# MOTOR_CONTROL.net
KiCad netlist of a schematic drawn in Altium Designer
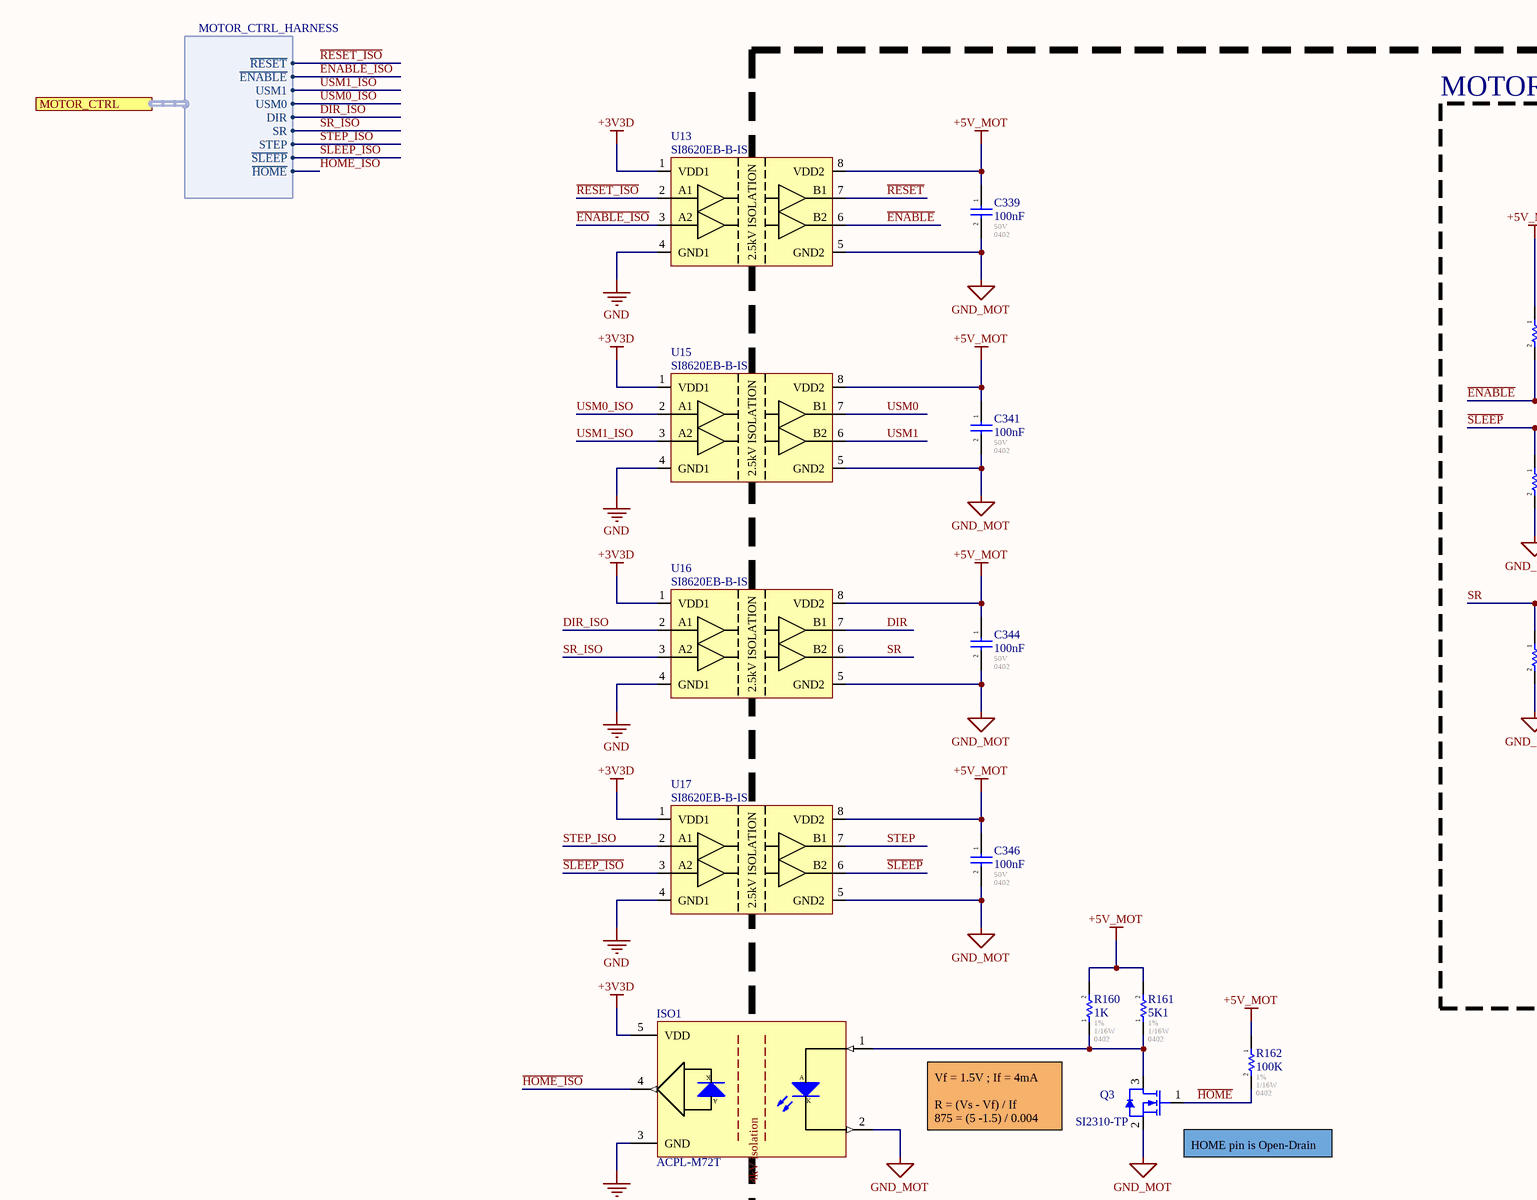
[diagram p0: MOTOR_CONTROL.SchDoc, top left]
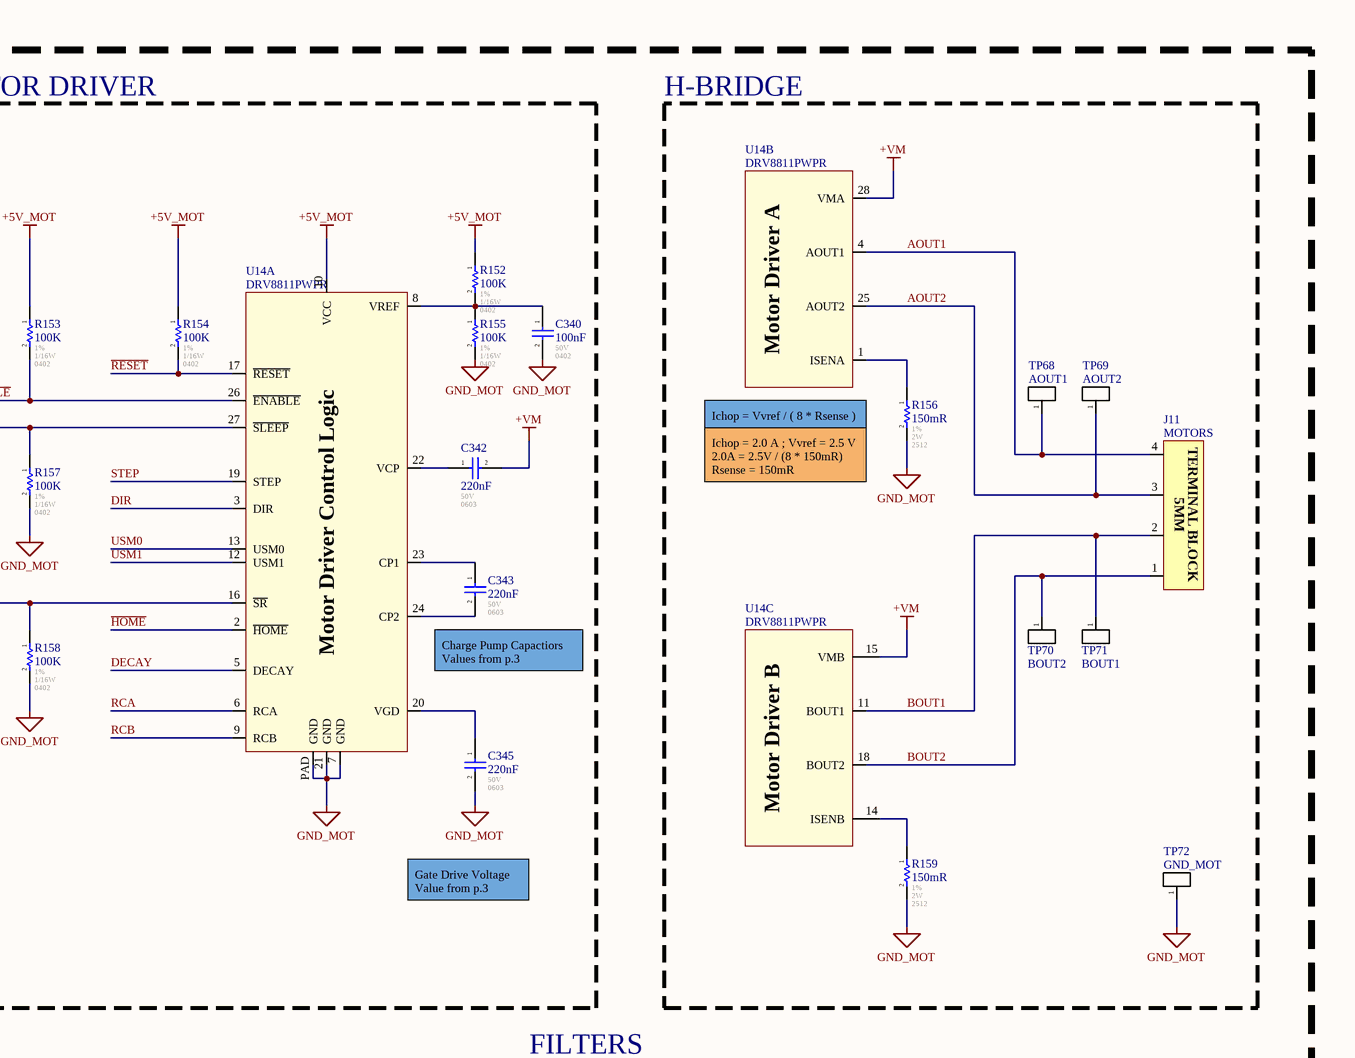
[diagram p1: MOTOR_CONTROL.SchDoc, top right]
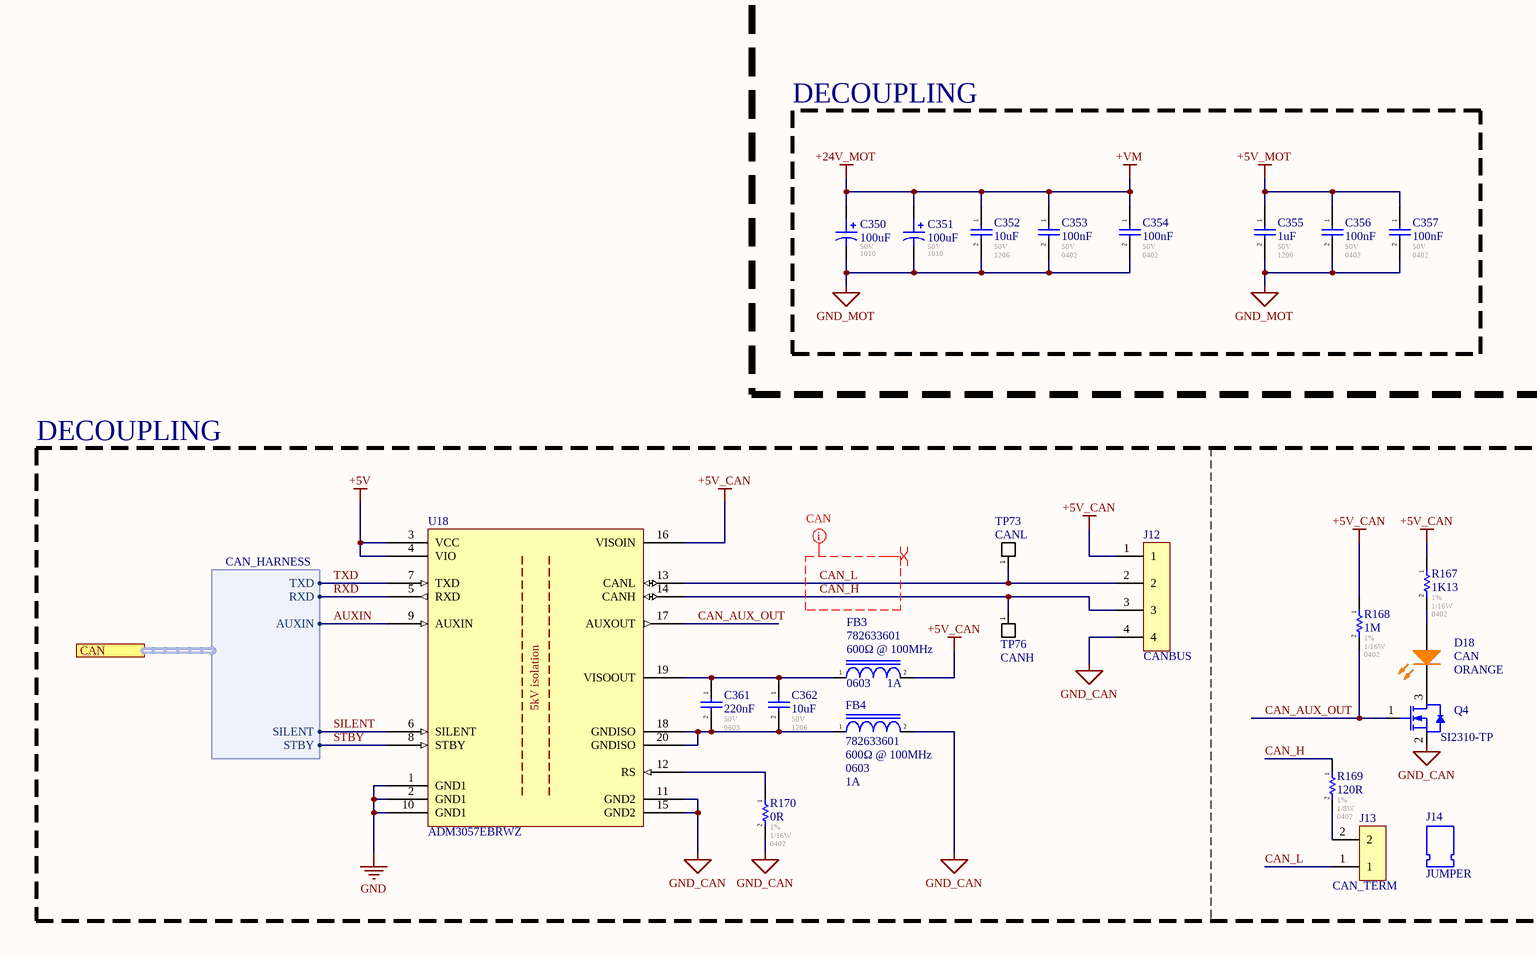
[diagram p2: MOTOR_CONTROL.SchDoc, bottom left]
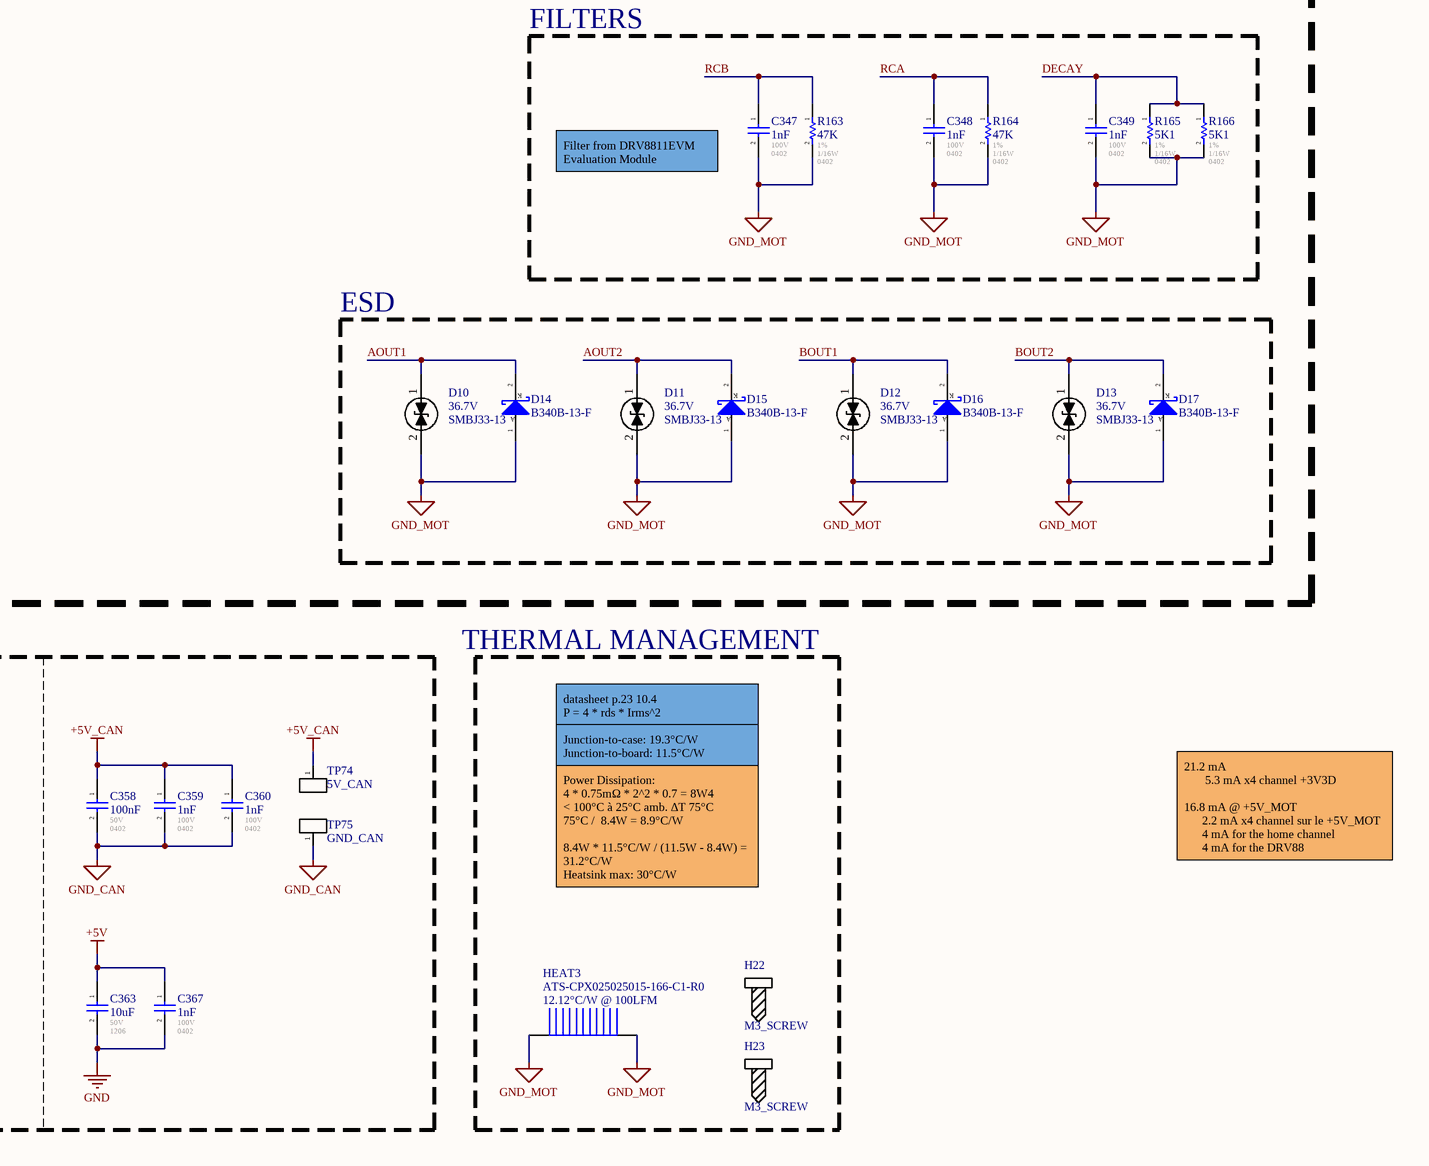
[diagram p3: MOTOR_CONTROL.SchDoc, bottom right]

(export (version "E")
  (design (tool "Eeschema 10.0.6"))
  (components
    (comp (ref "C339")
      (value "100nF")
      (footprint "0402")
      (description "GCM155R71H104KE02J\r\n0402 100nF 10% X7R Ceramic Capacitor")
      (fields
        (field (name "MFR") "Murata")
        (field (name "PART#") "GCM155R71H104KE02J")
        (field (name "VOLTAGE - RATED") "50V")
      )
      (libsource (lib "Symbols") (part "CAP_CER"))
    )
    (comp (ref "C340")
      (value "100nF")
      (footprint "0402")
      (description "GCM155R71H104KE02J\r\n0402 100nF 10% X7R Ceramic Capacitor")
      (fields
        (field (name "MFR") "Murata")
        (field (name "PART#") "GCM155R71H104KE02J")
        (field (name "VOLTAGE - RATED") "50V")
      )
      (libsource (lib "Symbols") (part "CAP_CER"))
    )
    (comp (ref "C341")
      (value "100nF")
      (footprint "0402")
      (description "GCM155R71H104KE02J\r\n0402 100nF 10% X7R Ceramic Capacitor")
      (fields
        (field (name "MFR") "Murata")
        (field (name "PART#") "GCM155R71H104KE02J")
        (field (name "VOLTAGE - RATED") "50V")
      )
      (libsource (lib "Symbols") (part "CAP_CER"))
    )
    (comp (ref "C342")
      (value "220nF")
      (footprint "0603")
      (description "GCM188R71H224KA64D\r\n0603 220nF 10% X7R Ceramic Capacitor")
      (fields
        (field (name "MFR") "Murata")
        (field (name "PART#") "GCM188R71H224KA64D")
        (field (name "VOLTAGE - RATED") "50V")
      )
      (libsource (lib "Symbols") (part "CAP_CER"))
    )
    (comp (ref "C343")
      (value "220nF")
      (footprint "0603")
      (description "GCM188R71H224KA64D\r\n0603 220nF 10% X7R Ceramic Capacitor")
      (fields
        (field (name "MFR") "Murata")
        (field (name "PART#") "GCM188R71H224KA64D")
        (field (name "VOLTAGE - RATED") "50V")
      )
      (libsource (lib "Symbols") (part "CAP_CER"))
    )
    (comp (ref "C344")
      (value "100nF")
      (footprint "0402")
      (description "GCM155R71H104KE02J\r\n0402 100nF 10% X7R Ceramic Capacitor")
      (fields
        (field (name "MFR") "Murata")
        (field (name "PART#") "GCM155R71H104KE02J")
        (field (name "VOLTAGE - RATED") "50V")
      )
      (libsource (lib "Symbols") (part "CAP_CER"))
    )
    (comp (ref "C345")
      (value "220nF")
      (footprint "0603")
      (description "GCM188R71H224KA64D\r\n0603 220nF 10% X7R Ceramic Capacitor")
      (fields
        (field (name "MFR") "Murata")
        (field (name "PART#") "GCM188R71H224KA64D")
        (field (name "VOLTAGE - RATED") "50V")
      )
      (libsource (lib "Symbols") (part "CAP_CER"))
    )
    (comp (ref "C346")
      (value "100nF")
      (footprint "0402")
      (description "GCM155R71H104KE02J\r\n0402 100nF 10% X7R Ceramic Capacitor")
      (fields
        (field (name "MFR") "Murata")
        (field (name "PART#") "GCM155R71H104KE02J")
        (field (name "VOLTAGE - RATED") "50V")
      )
      (libsource (lib "Symbols") (part "CAP_CER"))
    )
    (comp (ref "C347")
      (value "1nF")
      (footprint "0402")
      (description "GCM155R72A102KA37D\r\n0402 1nF 10% X7R Ceramic Capacitor")
      (fields
        (field (name "MFR") "Murata")
        (field (name "PART#") "GCM155R72A102KA37D")
        (field (name "VOLTAGE - RATED") "100V")
      )
      (libsource (lib "Symbols") (part "CAP_CER"))
    )
    (comp (ref "C348")
      (value "1nF")
      (footprint "0402")
      (description "GCM155R72A102KA37D\r\n0402 1nF 10% X7R Ceramic Capacitor")
      (fields
        (field (name "MFR") "Murata")
        (field (name "PART#") "GCM155R72A102KA37D")
        (field (name "VOLTAGE - RATED") "100V")
      )
      (libsource (lib "Symbols") (part "CAP_CER"))
    )
    (comp (ref "C349")
      (value "1nF")
      (footprint "0402")
      (description "GCM155R72A102KA37D\r\n0402 1nF 10% X7R Ceramic Capacitor")
      (fields
        (field (name "MFR") "Murata")
        (field (name "PART#") "GCM155R72A102KA37D")
        (field (name "VOLTAGE - RATED") "100V")
      )
      (libsource (lib "Symbols") (part "CAP_CER"))
    )
    (comp (ref "C350")
      (value "100uF")
      (footprint "CAP_ALU_1010_vishay")
      (description "CAP - ALU 100uF 20% 50V - 1010")
      (fields
        (field (name "MFG") "Vishay Dale")
        (field (name "MFG PART NUMBER") "MAL215099101E3")
        (field (name "VOLTAGE") "50V")
        (field (name "PACKAGE") "1010")
        (field (name "CREATEDBY") "Jonathan Bouchard")
      )
      (libsource (lib "S7CAS_LIB2023") (part "CAP_ALU_MAL215099101E3"))
    )
    (comp (ref "C351")
      (value "100uF")
      (footprint "CAP_ALU_1010_vishay")
      (description "CAP - ALU 100uF 20% 50V - 1010")
      (fields
        (field (name "MFG") "Vishay Dale")
        (field (name "MFG PART NUMBER") "MAL215099101E3")
        (field (name "VOLTAGE") "50V")
        (field (name "PACKAGE") "1010")
        (field (name "CREATEDBY") "Jonathan Bouchard")
      )
      (libsource (lib "S7CAS_LIB2023") (part "CAP_ALU_MAL215099101E3"))
    )
    (comp (ref "C352")
      (value "10uF")
      (footprint "1206")
      (description "GRT31CR61H106KE01L\r\n1206 10uF 10% X5R Ceramic Capacitor")
      (fields
        (field (name "MFR") "Murata")
        (field (name "VOLTAGE - RATED") "50V")
        (field (name "TOLERANCE") "10%")
      )
      (libsource (lib "Symbols") (part "CAP_CER"))
    )
    (comp (ref "C353")
      (value "100nF")
      (footprint "0402")
      (description "GCM155R71H104KE02J\r\n0402 100nF 10% X7R Ceramic Capacitor")
      (fields
        (field (name "MFR") "Murata")
        (field (name "PART#") "GCM155R71H104KE02J")
        (field (name "VOLTAGE - RATED") "50V")
      )
      (libsource (lib "Symbols") (part "CAP_CER"))
    )
    (comp (ref "C354")
      (value "100nF")
      (footprint "0402")
      (description "GCM155R71H104KE02J\r\n0402 100nF 10% X7R Ceramic Capacitor")
      (fields
        (field (name "MFR") "Murata")
        (field (name "PART#") "GCM155R71H104KE02J")
        (field (name "VOLTAGE - RATED") "50V")
      )
      (libsource (lib "Symbols") (part "CAP_CER"))
    )
    (comp (ref "C355")
      (value "1uF")
      (footprint "1206")
      (description "GCJ31CR71H105KA12L\r\n1206 1uF 10% X7R Ceramic Capacitor")
      (fields
        (field (name "MFR") "Murata")
        (field (name "PART#") "GCJ31CR71H105KA12L")
        (field (name "VOLTAGE - RATED") "50V")
      )
      (libsource (lib "Symbols") (part "CAP_CER"))
    )
    (comp (ref "C356")
      (value "100nF")
      (footprint "0402")
      (description "GCM155R71H104KE02J\r\n0402 100nF 10% X7R Ceramic Capacitor")
      (fields
        (field (name "MFR") "Murata")
        (field (name "PART#") "GCM155R71H104KE02J")
        (field (name "VOLTAGE - RATED") "50V")
      )
      (libsource (lib "Symbols") (part "CAP_CER"))
    )
    (comp (ref "C357")
      (value "100nF")
      (footprint "0402")
      (description "GCM155R71H104KE02J\r\n0402 100nF 10% X7R Ceramic Capacitor")
      (fields
        (field (name "MFR") "Murata")
        (field (name "PART#") "GCM155R71H104KE02J")
        (field (name "VOLTAGE - RATED") "50V")
      )
      (libsource (lib "Symbols") (part "CAP_CER"))
    )
    (comp (ref "C358")
      (value "100nF")
      (footprint "0402")
      (description "GCM155R71H104KE02J\r\n0402 100nF 10% X7R Ceramic Capacitor")
      (fields
        (field (name "MFR") "Murata")
        (field (name "PART#") "GCM155R71H104KE02J")
        (field (name "VOLTAGE - RATED") "50V")
      )
      (libsource (lib "Symbols") (part "CAP_CER"))
    )
    (comp (ref "C359")
      (value "1nF")
      (footprint "0402")
      (description "GCM155R72A102KA37D\r\n0402 1nF 10% X7R Ceramic Capacitor")
      (fields
        (field (name "MFR") "Murata")
        (field (name "PART#") "GCM155R72A102KA37D")
        (field (name "VOLTAGE - RATED") "100V")
      )
      (libsource (lib "Symbols") (part "CAP_CER"))
    )
    (comp (ref "C360")
      (value "1nF")
      (footprint "0402")
      (description "GCM155R72A102KA37D\r\n0402 1nF 10% X7R Ceramic Capacitor")
      (fields
        (field (name "MFR") "Murata")
        (field (name "PART#") "GCM155R72A102KA37D")
        (field (name "VOLTAGE - RATED") "100V")
      )
      (libsource (lib "Symbols") (part "CAP_CER"))
    )
    (comp (ref "C361")
      (value "220nF")
      (footprint "0603")
      (description "GCM188R71H224KA64D\r\n0603 220nF 10% X7R Ceramic Capacitor")
      (fields
        (field (name "MFR") "Murata")
        (field (name "PART#") "GCM188R71H224KA64D")
        (field (name "VOLTAGE - RATED") "50V")
      )
      (libsource (lib "Symbols") (part "CAP_CER"))
    )
    (comp (ref "C362")
      (value "10uF")
      (footprint "1206")
      (description "GRT31CR61H106KE01L\r\n1206 10uF 10% X5R Ceramic Capacitor")
      (fields
        (field (name "MFR") "Murata")
        (field (name "VOLTAGE - RATED") "50V")
        (field (name "TOLERANCE") "10%")
      )
      (libsource (lib "Symbols") (part "CAP_CER"))
    )
    (comp (ref "C363")
      (value "10uF")
      (footprint "1206")
      (description "GRT31CR61H106KE01L\r\n1206 10uF 10% X5R Ceramic Capacitor")
      (fields
        (field (name "MFR") "Murata")
        (field (name "VOLTAGE - RATED") "50V")
        (field (name "TOLERANCE") "10%")
      )
      (libsource (lib "Symbols") (part "CAP_CER"))
    )
    (comp (ref "C367")
      (value "1nF")
      (footprint "0402")
      (description "GCM155R72A102KA37D\r\n0402 1nF 10% X7R Ceramic Capacitor")
      (fields
        (field (name "MFR") "Murata")
        (field (name "PART#") "GCM155R72A102KA37D")
        (field (name "VOLTAGE - RATED") "100V")
      )
      (libsource (lib "Symbols") (part "CAP_CER"))
    )
    (comp (ref "D10")
      (value "SMBJ33-13")
      (footprint "DO214AA (SMB)")
      (description "53.3V Clamp 11.3A Ipp Tvs Diode Surface Mount SMB")
      (fields (field (name "MFR") "SMBJ33CAQ-13-F") (field (name "VOLTAGE - BREAKDOWN") "36.7V"))
      (libsource (lib "Symbols") (part "DIODE_TVS"))
    )
    (comp (ref "D11")
      (value "SMBJ33-13")
      (footprint "DO214AA (SMB)")
      (description "53.3V Clamp 11.3A Ipp Tvs Diode Surface Mount SMB")
      (fields (field (name "MFR") "SMBJ33CAQ-13-F") (field (name "VOLTAGE - BREAKDOWN") "36.7V"))
      (libsource (lib "Symbols") (part "DIODE_TVS"))
    )
    (comp (ref "D12")
      (value "SMBJ33-13")
      (footprint "DO214AA (SMB)")
      (description "53.3V Clamp 11.3A Ipp Tvs Diode Surface Mount SMB")
      (fields (field (name "MFR") "SMBJ33CAQ-13-F") (field (name "VOLTAGE - BREAKDOWN") "36.7V"))
      (libsource (lib "Symbols") (part "DIODE_TVS"))
    )
    (comp (ref "D13")
      (value "SMBJ33-13")
      (footprint "DO214AA (SMB)")
      (description "53.3V Clamp 11.3A Ipp Tvs Diode Surface Mount SMB")
      (fields (field (name "MFR") "SMBJ33CAQ-13-F") (field (name "VOLTAGE - BREAKDOWN") "36.7V"))
      (libsource (lib "Symbols") (part "DIODE_TVS"))
    )
    (comp (ref "D14")
      (value "B340B-13-F")
      (footprint "DO214AA (SMB)")
      (description "Generic Shottkey Diode")
      (fields (field (name "MFR") "Diodes Incorporated"))
      (libsource (lib "Symbols") (part "DIODE_SHOTTKEY"))
    )
    (comp (ref "D15")
      (value "B340B-13-F")
      (footprint "DO214AA (SMB)")
      (description "Generic Shottkey Diode")
      (fields (field (name "MFR") "Diodes Incorporated"))
      (libsource (lib "Symbols") (part "DIODE_SHOTTKEY"))
    )
    (comp (ref "D16")
      (value "B340B-13-F")
      (footprint "DO214AA (SMB)")
      (description "Generic Shottkey Diode")
      (fields (field (name "MFR") "Diodes Incorporated"))
      (libsource (lib "Symbols") (part "DIODE_SHOTTKEY"))
    )
    (comp (ref "D17")
      (value "B340B-13-F")
      (footprint "DO214AA (SMB)")
      (description "Generic Shottkey Diode")
      (fields (field (name "MFR") "Diodes Incorporated"))
      (libsource (lib "Symbols") (part "DIODE_SHOTTKEY"))
    )
    (comp (ref "D18")
      (value "CAN")
      (footprint "LED_0603")
      (description "LED - 611nM ORANGE 2mA - 0603")
      (fields
        (field (name "VOLTAGE") "1.8V")
        (field (name "MFG") "ROHM Semiconductor")
        (field (name "ALTIUM_VALUE") "ORANGE")
        (field (name "CREATEDBY") "Jonathan Bouchard")
      )
      (libsource (lib "S7CAS_LIB2023") (part "LED_SML-311DTT86"))
    )
    (comp (ref "FB3")
      (value "782633601")
      (footprint "IND_0603")
      (description "600 Ohms @ 100 MHz 1 Signal Line Ferrite Bead 0603 (1608 Metric) 1A 200mOhm")
      (fields
        (field (name "IMPEDANCE @ FREQ") "600Ω @ 100MHz")
        (field (name "PACKAGE / CASE") "0603")
        (field (name "CURRENT RATING") "1A")
        (field (name "MANUFACTURER") "Wurth Elektronik")
      )
      (libsource (lib "Symbols") (part "FERRITE_BEAD"))
    )
    (comp (ref "FB4")
      (value "782633601")
      (footprint "IND_0603")
      (description "600 Ohms @ 100 MHz 1 Signal Line Ferrite Bead 0603 (1608 Metric) 1A 200mOhm")
      (fields
        (field (name "IMPEDANCE @ FREQ") "600Ω @ 100MHz")
        (field (name "PACKAGE / CASE") "0603")
        (field (name "CURRENT RATING") "1A")
        (field (name "MANUFACTURER") "Wurth Elektronik")
      )
      (libsource (lib "Symbols") (part "FERRITE_BEAD"))
    )
    (comp (ref "H22") (value "M3_SCREW") (libsource (lib "Misc") (part "M3_screw")))
    (comp (ref "H23") (value "M3_SCREW") (libsource (lib "Misc") (part "M3_screw")))
    (comp (ref "HEAT3")
      (value "ATS-CPX025025015-166-C1-R0")
      (footprint "ATS-CPX025025015-166-C1-R0")
      (description "Heatsink Aluminium")
      (fields
        (field (name "MFR") "Advanced Thermal Solutions Inc.")
        (field (name "THERMAL RESISTANCE") "12.12°C/W @ 100LFM")
      )
      (libsource (lib "Misc") (part "HEATSINK_ATS-CPX025025015-166-C1-R0"))
    )
    (comp (ref "ISO1")
      (value "ACPL-M72T")
      (footprint "SOIC-5_4.4MM")
      (description "Logic Output Optoisolator Push-Pull, Totem Pole 4000Vrms 1 Channel 25kV/µs CMTI 5-SO")
      (fields (field (name "MFR") "Broadcom Limited"))
      (libsource (lib "Misc") (part "ACPL-M72T"))
    )
    (comp (ref "J11")
      (value "MOTORS")
      (footprint "CONN_TERMINAL_OSTTA040161")
      (description "CONN -  TERMINAL BLOCK 4POS 5MM - TH")
      (fields
        (field (name "MFG") "On Shore Technology Inc.")
        (field (name "MFG PART NUMBER") "OSTTC040162")
        (field (name "CREATEDBY") "Jonathan Bouchard")
      )
      (libsource (lib "S7CAS_LIB2023") (part "CONN_TERMINAL_OSTTC040162"))
    )
    (comp (ref "J12")
      (value "CANBUS")
      (footprint "HEADER-4_100MIL")
      (libsource (lib "Connectors") (part "HEADER_4"))
    )
    (comp (ref "J13")
      (value "CAN_TERM")
      (footprint "HEADER-2_100MIL")
      (libsource (lib "Connectors") (part "HEADER_2"))
    )
    (comp (ref "J14") (value "JUMPER") (libsource (lib "Misc") (part "JUMPER")))
    (comp (ref "Q3")
      (value "SI2310-TP")
      (footprint "TRX_NMOS_SI2310-TP")
      (description "TRX - MOSFET N-CH 60V 3A - SOT-23")
      (fields
        (field (name "CREATEDBY/DATE") "Louis-Daniel Gaulin / 20-02-2020")
        (field (name "VERIFIEDBY") "C.Paulin - 21/02/2020")
      )
      (libsource (lib "S7CAS_LIB2023") (part "TRX_NMOS_SI2310-TP"))
    )
    (comp (ref "Q4")
      (value "SI2310-TP")
      (footprint "TRX_NMOS_SI2310-TP")
      (description "TRX - MOSFET N-CH 60V 3A - SOT-23")
      (fields
        (field (name "CREATEDBY/DATE") "Louis-Daniel Gaulin / 20-02-2020")
        (field (name "VERIFIEDBY") "C.Paulin - 21/02/2020")
      )
      (libsource (lib "S7CAS_LIB2023") (part "TRX_NMOS_SI2310-TP"))
    )
    (comp (ref "R152")
      (value "100K")
      (footprint "RES_0402")
      (fields
        (field (name "TOLERANCE") "1%")
        (field (name "POWER") "1/16W")
        (field (name "PACKAGE / CASE") "0402")
      )
      (libsource (lib "Symbols") (part "RESISTOR"))
    )
    (comp (ref "R153")
      (value "100K")
      (footprint "RES_0402")
      (fields
        (field (name "TOLERANCE") "1%")
        (field (name "POWER") "1/16W")
        (field (name "PACKAGE / CASE") "0402")
      )
      (libsource (lib "Symbols") (part "RESISTOR"))
    )
    (comp (ref "R154")
      (value "100K")
      (footprint "RES_0402")
      (fields
        (field (name "TOLERANCE") "1%")
        (field (name "POWER") "1/16W")
        (field (name "PACKAGE / CASE") "0402")
      )
      (libsource (lib "Symbols") (part "RESISTOR"))
    )
    (comp (ref "R155")
      (value "100K")
      (footprint "RES_0402")
      (fields
        (field (name "TOLERANCE") "1%")
        (field (name "POWER") "1/16W")
        (field (name "PACKAGE / CASE") "0402")
      )
      (libsource (lib "Symbols") (part "RESISTOR"))
    )
    (comp (ref "R156")
      (value "150mR")
      (footprint "RES_2512")
      (description "CSRN2512FKR150")
      (fields
        (field (name "TOLERANCE") "1%")
        (field (name "POWER") "2W")
        (field (name "PACKAGE / CASE") "2512")
      )
      (libsource (lib "Symbols") (part "RESISTOR"))
    )
    (comp (ref "R157")
      (value "100K")
      (footprint "RES_0402")
      (fields
        (field (name "TOLERANCE") "1%")
        (field (name "POWER") "1/16W")
        (field (name "PACKAGE / CASE") "0402")
      )
      (libsource (lib "Symbols") (part "RESISTOR"))
    )
    (comp (ref "R158")
      (value "100K")
      (footprint "RES_0402")
      (fields
        (field (name "TOLERANCE") "1%")
        (field (name "POWER") "1/16W")
        (field (name "PACKAGE / CASE") "0402")
      )
      (libsource (lib "Symbols") (part "RESISTOR"))
    )
    (comp (ref "R159")
      (value "150mR")
      (footprint "RES_2512")
      (description "CSRN2512FKR150")
      (fields
        (field (name "TOLERANCE") "1%")
        (field (name "POWER") "2W")
        (field (name "PACKAGE / CASE") "2512")
      )
      (libsource (lib "Symbols") (part "RESISTOR"))
    )
    (comp (ref "R160")
      (value "1K")
      (footprint "RES_0402")
      (fields
        (field (name "TOLERANCE") "1%")
        (field (name "POWER") "1/16W")
        (field (name "PACKAGE / CASE") "0402")
      )
      (libsource (lib "Symbols") (part "RESISTOR"))
    )
    (comp (ref "R161")
      (value "5K1")
      (footprint "RES_0402")
      (fields
        (field (name "TOLERANCE") "1%")
        (field (name "POWER") "1/16W")
        (field (name "PACKAGE / CASE") "0402")
      )
      (libsource (lib "Symbols") (part "RESISTOR"))
    )
    (comp (ref "R162")
      (value "100K")
      (footprint "RES_0402")
      (fields
        (field (name "TOLERANCE") "1%")
        (field (name "POWER") "1/16W")
        (field (name "PACKAGE / CASE") "0402")
      )
      (libsource (lib "Symbols") (part "RESISTOR"))
    )
    (comp (ref "R163")
      (value "47K")
      (footprint "RES_0402")
      (fields
        (field (name "TOLERANCE") "1%")
        (field (name "POWER") "1/16W")
        (field (name "PACKAGE / CASE") "0402")
      )
      (libsource (lib "Symbols") (part "RESISTOR"))
    )
    (comp (ref "R164")
      (value "47K")
      (footprint "RES_0402")
      (fields
        (field (name "TOLERANCE") "1%")
        (field (name "POWER") "1/16W")
        (field (name "PACKAGE / CASE") "0402")
      )
      (libsource (lib "Symbols") (part "RESISTOR"))
    )
    (comp (ref "R165")
      (value "5K1")
      (footprint "RES_0402")
      (fields
        (field (name "TOLERANCE") "1%")
        (field (name "POWER") "1/16W")
        (field (name "PACKAGE / CASE") "0402")
      )
      (libsource (lib "Symbols") (part "RESISTOR"))
    )
    (comp (ref "R166")
      (value "5K1")
      (footprint "RES_0402")
      (fields
        (field (name "TOLERANCE") "1%")
        (field (name "POWER") "1/16W")
        (field (name "PACKAGE / CASE") "0402")
      )
      (libsource (lib "Symbols") (part "RESISTOR"))
    )
    (comp (ref "R167")
      (value "1K13")
      (footprint "RES_0402")
      (fields
        (field (name "TOLERANCE") "1%")
        (field (name "POWER") "1/16W")
        (field (name "PACKAGE / CASE") "0402")
      )
      (libsource (lib "Symbols") (part "RESISTOR"))
    )
    (comp (ref "R168")
      (value "1M")
      (footprint "RES_0402")
      (description "1M 0402 1% 1/16W Resistor")
      (fields
        (field (name "TOLERANCE") "1%")
        (field (name "POWER") "1/16W")
        (field (name "PACKAGE / CASE") "0402")
      )
      (libsource (lib "Symbols") (part "RESISTOR"))
    )
    (comp (ref "R169")
      (value "120R")
      (footprint "RES_0402")
      (fields
        (field (name "TOLERANCE") "1%")
        (field (name "POWER") "1/8W")
        (field (name "PACKAGE / CASE") "0402")
      )
      (libsource (lib "Symbols") (part "RESISTOR"))
    )
    (comp (ref "R170")
      (value "0R")
      (footprint "RES_0402")
      (fields
        (field (name "TOLERANCE") "1%")
        (field (name "POWER") "1/16W")
        (field (name "PACKAGE / CASE") "0402")
      )
      (libsource (lib "Symbols") (part "RESISTOR"))
    )
    (comp (ref "TP68")
      (value "AOUT1")
      (footprint "TP_HOLE")
      (description "Test Point")
      (libsource (lib "Symbols") (part "TESTPOINT"))
    )
    (comp (ref "TP69")
      (value "AOUT2")
      (footprint "TP_HOLE")
      (description "Test Point")
      (libsource (lib "Symbols") (part "TESTPOINT"))
    )
    (comp (ref "TP70")
      (value "BOUT2")
      (footprint "TP_HOLE")
      (description "Test Point")
      (libsource (lib "Symbols") (part "TESTPOINT"))
    )
    (comp (ref "TP71")
      (value "BOUT1")
      (footprint "TP_HOLE")
      (description "Test Point")
      (libsource (lib "Symbols") (part "TESTPOINT"))
    )
    (comp (ref "TP72")
      (value "GND_MOT")
      (footprint "TP_HOLE")
      (description "Test Point")
      (libsource (lib "Symbols") (part "TESTPOINT"))
    )
    (comp (ref "TP73")
      (value "CANL")
      (footprint "TP_PAD")
      (description "Test Point")
      (libsource (lib "Symbols") (part "TESTPOINT_PAD"))
    )
    (comp (ref "TP74")
      (value "5V_CAN")
      (footprint "TP_HOLE")
      (description "Test Point")
      (libsource (lib "Symbols") (part "TESTPOINT"))
    )
    (comp (ref "TP75")
      (value "GND_CAN")
      (footprint "TP_HOLE")
      (description "Test Point")
      (libsource (lib "Symbols") (part "TESTPOINT"))
    )
    (comp (ref "TP76")
      (value "CANH")
      (footprint "TP_PAD")
      (description "Test Point")
      (libsource (lib "Symbols") (part "TESTPOINT_PAD"))
    )
    (comp (ref "U13")
      (value "SI8620EB-B-IS")
      (footprint "ISO_SI8620EB-B-IS")
      (description "ISO - Dual-Channel Digital Isolator (default HI) - 8-SOIC")
      (fields
        (field (name "CREATEDBY/DATE") "Joel Lemay 2018-06-05")
        (field (name "VERIFIEDBY") "Caroline Paulin - 12 sept 2018")
      )
      (libsource (lib "S7CAS_LIB2023") (part "ISO_SI8620EB-B-IS"))
    )
    (comp (ref "U14")
      (value "DRV8811PWPR")
      (footprint "POW_MOTOR_DRV8811PWPR")
      (description "POW - STEPPER MOTOR DRIVER - SOP-28")
      (fields
        (field (name "VOLTAGE") "3 V ~ 5.5 V / 8 V ~ 38 V")
        (field (name "MFG") "Texas Instrument")
        (field (name "CREATEDBY") "Jonathan Bouchard")
      )
      (libsource (lib "S7CAS_LIB2023") (part "POW_MOTOR_DRV8811PWPR"))
    )
    (comp (ref "U15")
      (value "SI8620EB-B-IS")
      (footprint "ISO_SI8620EB-B-IS")
      (description "ISO - Dual-Channel Digital Isolator (default HI) - 8-SOIC")
      (fields
        (field (name "CREATEDBY/DATE") "Joel Lemay 2018-06-05")
        (field (name "VERIFIEDBY") "Caroline Paulin - 12 sept 2018")
      )
      (libsource (lib "S7CAS_LIB2023") (part "ISO_SI8620EB-B-IS"))
    )
    (comp (ref "U16")
      (value "SI8620EB-B-IS")
      (footprint "ISO_SI8620EB-B-IS")
      (description "ISO - Dual-Channel Digital Isolator (default HI) - 8-SOIC")
      (fields
        (field (name "CREATEDBY/DATE") "Joel Lemay 2018-06-05")
        (field (name "VERIFIEDBY") "Caroline Paulin - 12 sept 2018")
      )
      (libsource (lib "S7CAS_LIB2023") (part "ISO_SI8620EB-B-IS"))
    )
    (comp (ref "U17")
      (value "SI8620EB-B-IS")
      (footprint "ISO_SI8620EB-B-IS")
      (description "ISO - Dual-Channel Digital Isolator (default HI) - 8-SOIC")
      (fields
        (field (name "CREATEDBY/DATE") "Joel Lemay 2018-06-05")
        (field (name "VERIFIEDBY") "Caroline Paulin - 12 sept 2018")
      )
      (libsource (lib "S7CAS_LIB2023") (part "ISO_SI8620EB-B-IS"))
    )
    (comp (ref "U18")
      (value "ADM3057EBRWZ")
      (footprint "SOIC-20_7.5mm")
      (description "1/1 Transceiver, Isolated CANbus 20-SOIC")
      (fields (field (name "MFR") "Analog Devices"))
      (libsource (lib "Misc") (part "ADM3057EBRWZ"))
    )
  )
  (nets
    (net (code "3") (name "+3V3D") (class "Default")
      (node (ref "ISO1") (pin "5") (pinfunction "VDD_5") (pintype "power_in"))
      (node (ref "U13") (pin "1") (pinfunction "VDD1_1") (pintype "passive"))
      (node (ref "U15") (pin "1") (pinfunction "VDD1_1") (pintype "passive"))
      (node (ref "U16") (pin "1") (pinfunction "VDD1_1") (pintype "passive"))
      (node (ref "U17") (pin "1") (pinfunction "VDD1_1") (pintype "passive"))
    )
    (net (code "4") (name "+5V") (class "Default")
      (node (ref "C363") (pin "1") (pinfunction "1_1") (pintype "passive"))
      (node (ref "C367") (pin "1") (pinfunction "1_1") (pintype "passive"))
      (node (ref "U18") (pin "3") (pinfunction "VCC_3") (pintype "power_in"))
      (node (ref "U18") (pin "4") (pinfunction "VIO_4") (pintype "power_in"))
    )
    (net (code "5") (name "+5V_CAN") (class "Default")
      (node (ref "C358") (pin "1") (pinfunction "1_1") (pintype "passive"))
      (node (ref "C359") (pin "1") (pinfunction "1_1") (pintype "passive"))
      (node (ref "C360") (pin "1") (pinfunction "1_1") (pintype "passive"))
      (node (ref "FB3") (pin "2") (pinfunction "2_2") (pintype "passive"))
      (node (ref "J12") (pin "1") (pinfunction "1_1") (pintype "passive"))
      (node (ref "R167") (pin "1") (pinfunction "1_1") (pintype "passive"))
      (node (ref "R168") (pin "1") (pinfunction "1_1") (pintype "passive"))
      (node (ref "TP74") (pin "1") (pinfunction "A_1") (pintype "passive"))
      (node (ref "U18") (pin "16") (pinfunction "VISOIN_16") (pintype "power_in"))
    )
    (net (code "6") (name "+5V_MOT") (class "Default")
      (node (ref "C339") (pin "1") (pinfunction "1_1") (pintype "passive"))
      (node (ref "C341") (pin "1") (pinfunction "1_1") (pintype "passive"))
      (node (ref "C344") (pin "1") (pinfunction "1_1") (pintype "passive"))
      (node (ref "C346") (pin "1") (pinfunction "1_1") (pintype "passive"))
      (node (ref "C355") (pin "1") (pinfunction "1_1") (pintype "passive"))
      (node (ref "C356") (pin "1") (pinfunction "1_1") (pintype "passive"))
      (node (ref "C357") (pin "1") (pinfunction "1_1") (pintype "passive"))
      (node (ref "R152") (pin "1") (pinfunction "1_1") (pintype "passive"))
      (node (ref "R153") (pin "1") (pinfunction "1_1") (pintype "passive"))
      (node (ref "R154") (pin "1") (pinfunction "1_1") (pintype "passive"))
      (node (ref "R160") (pin "2") (pinfunction "2_2") (pintype "passive"))
      (node (ref "R161") (pin "2") (pinfunction "2_2") (pintype "passive"))
      (node (ref "R162") (pin "1") (pinfunction "1_1") (pintype "passive"))
      (node (ref "U13") (pin "8") (pinfunction "VDD2_8") (pintype "passive"))
      (node (ref "U14") (pin "10") (pinfunction "VCC_10") (pintype "passive"))
      (node (ref "U15") (pin "8") (pinfunction "VDD2_8") (pintype "passive"))
      (node (ref "U16") (pin "8") (pinfunction "VDD2_8") (pintype "passive"))
      (node (ref "U17") (pin "8") (pinfunction "VDD2_8") (pintype "passive"))
    )
    (net (code "7") (name "+24V_MOT") (class "Default")
      (node (ref "C342") (pin "2") (pinfunction "2_2") (pintype "passive"))
      (node (ref "C350") (pin "1") (pinfunction "1_1") (pintype "passive"))
      (node (ref "C351") (pin "1") (pinfunction "1_1") (pintype "passive"))
      (node (ref "C352") (pin "1") (pinfunction "1_1") (pintype "passive"))
      (node (ref "C353") (pin "1") (pinfunction "1_1") (pintype "passive"))
      (node (ref "C354") (pin "1") (pinfunction "1_1") (pintype "passive"))
      (node (ref "U14") (pin "15") (pinfunction "VMB_15") (pintype "passive"))
      (node (ref "U14") (pin "28") (pinfunction "VMA_28") (pintype "passive"))
    )
    (net (code "8") (name "/AOUT1") (class "Default")
      (node (ref "D10") (pin "1") (pinfunction "A_1") (pintype "passive"))
      (node (ref "D14") (pin "2") (pinfunction "K_2") (pintype "passive"))
      (node (ref "J11") (pin "4") (pinfunction "4_4") (pintype "passive"))
      (node (ref "TP68") (pin "1") (pinfunction "A_1") (pintype "passive"))
      (node (ref "U14") (pin "4") (pinfunction "AOUT1_4") (pintype "passive"))
    )
    (net (code "9") (name "/AOUT2") (class "Default")
      (node (ref "D11") (pin "1") (pinfunction "A_1") (pintype "passive"))
      (node (ref "D15") (pin "2") (pinfunction "K_2") (pintype "passive"))
      (node (ref "J11") (pin "3") (pinfunction "3_3") (pintype "passive"))
      (node (ref "TP69") (pin "1") (pinfunction "A_1") (pintype "passive"))
      (node (ref "U14") (pin "25") (pinfunction "AOUT2_25") (pintype "passive"))
    )
    (net (code "10") (name "/AUXIN") (class "Default")
      (node (ref "U18") (pin "9") (pinfunction "AUXIN_9") (pintype "input"))
    )
    (net (code "11") (name "/BOUT1") (class "Default")
      (node (ref "D12") (pin "1") (pinfunction "A_1") (pintype "passive"))
      (node (ref "D16") (pin "2") (pinfunction "K_2") (pintype "passive"))
      (node (ref "J11") (pin "2") (pinfunction "2_2") (pintype "passive"))
      (node (ref "TP71") (pin "1") (pinfunction "A_1") (pintype "passive"))
      (node (ref "U14") (pin "11") (pinfunction "BOUT1_11") (pintype "passive"))
    )
    (net (code "12") (name "/BOUT2") (class "Default")
      (node (ref "D13") (pin "1") (pinfunction "A_1") (pintype "passive"))
      (node (ref "D17") (pin "2") (pinfunction "K_2") (pintype "passive"))
      (node (ref "J11") (pin "1") (pinfunction "1_1") (pintype "passive"))
      (node (ref "TP70") (pin "1") (pinfunction "A_1") (pintype "passive"))
      (node (ref "U14") (pin "18") (pinfunction "BOUT2_18") (pintype "passive"))
    )
    (net (code "13") (name "/CAN_AUX_OUT") (class "Default")
      (node (ref "Q4") (pin "1") (pinfunction "G_1") (pintype "passive"))
      (node (ref "R168") (pin "2") (pinfunction "2_2") (pintype "passive"))
      (node (ref "U18") (pin "17") (pinfunction "AUXOUT_17") (pintype "output"))
    )
    (net (code "14") (name "/CAN_H") (class "Default")
      (node (ref "J12") (pin "3") (pinfunction "3_3") (pintype "passive"))
      (node (ref "R169") (pin "1") (pinfunction "1_1") (pintype "passive"))
      (node (ref "TP76") (pin "1") (pinfunction "A_1") (pintype "passive"))
      (node (ref "U18") (pin "14") (pinfunction "CANH_14") (pintype "bidirectional"))
    )
    (net (code "15") (name "/CAN_L") (class "Default")
      (node (ref "J12") (pin "2") (pinfunction "2_2") (pintype "passive"))
      (node (ref "J13") (pin "1") (pinfunction "1_1") (pintype "passive"))
      (node (ref "TP73") (pin "1") (pinfunction "A_1") (pintype "passive"))
      (node (ref "U18") (pin "13") (pinfunction "CANL_13") (pintype "bidirectional"))
    )
    (net (code "16") (name "/DECAY") (class "Default")
      (node (ref "C349") (pin "1") (pinfunction "1_1") (pintype "passive"))
      (node (ref "R165") (pin "1") (pinfunction "1_1") (pintype "passive"))
      (node (ref "R166") (pin "1") (pinfunction "1_1") (pintype "passive"))
      (node (ref "U14") (pin "5") (pinfunction "DECAY_5") (pintype "passive"))
    )
    (net (code "17") (name "/DIR") (class "Default")
      (node (ref "U14") (pin "3") (pinfunction "DIR_3") (pintype "passive"))
      (node (ref "U16") (pin "7") (pinfunction "B1_7") (pintype "passive"))
    )
    (net (code "18") (name "/DIR_ISO") (class "Default")
      (node (ref "U16") (pin "2") (pinfunction "A1_2") (pintype "passive"))
    )
    (net (code "19") (name "/ENABLE") (class "Default")
      (node (ref "R153") (pin "2") (pinfunction "2_2") (pintype "passive"))
      (node (ref "U13") (pin "6") (pinfunction "B2_6") (pintype "passive"))
      (node (ref "U14") (pin "26") (pinfunction "~{ENABLE}_26") (pintype "passive"))
    )
    (net (code "20") (name "/ENABLE_ISO") (class "Default")
      (node (ref "U13") (pin "3") (pinfunction "A2_3") (pintype "passive"))
    )
    (net (code "21") (name "/HOME") (class "Default")
      (node (ref "Q3") (pin "1") (pinfunction "G_1") (pintype "passive"))
      (node (ref "R162") (pin "2") (pinfunction "2_2") (pintype "passive"))
      (node (ref "U14") (pin "2") (pinfunction "HOME_2") (pintype "passive"))
    )
    (net (code "22") (name "/HOME_ISO") (class "Default")
      (node (ref "ISO1") (pin "4") (pinfunction "VOUT_4") (pintype "output"))
    )
    (net (code "23") (name "/RCA") (class "Default")
      (node (ref "C348") (pin "1") (pinfunction "1_1") (pintype "passive"))
      (node (ref "R164") (pin "1") (pinfunction "1_1") (pintype "passive"))
      (node (ref "U14") (pin "6") (pinfunction "RCA_6") (pintype "passive"))
    )
    (net (code "24") (name "/RCB") (class "Default")
      (node (ref "C347") (pin "1") (pinfunction "1_1") (pintype "passive"))
      (node (ref "R163") (pin "1") (pinfunction "1_1") (pintype "passive"))
      (node (ref "U14") (pin "9") (pinfunction "RCB_9") (pintype "passive"))
    )
    (net (code "25") (name "/RESET") (class "Default")
      (node (ref "R154") (pin "2") (pinfunction "2_2") (pintype "passive"))
      (node (ref "U13") (pin "7") (pinfunction "B1_7") (pintype "passive"))
      (node (ref "U14") (pin "17") (pinfunction "~{RESET}_17") (pintype "passive"))
    )
    (net (code "26") (name "/RESET_ISO") (class "Default")
      (node (ref "U13") (pin "2") (pinfunction "A1_2") (pintype "passive"))
    )
    (net (code "27") (name "/RXD") (class "Default")
      (node (ref "U18") (pin "5") (pinfunction "RXD_5") (pintype "output"))
    )
    (net (code "28") (name "/SILENT") (class "Default")
      (node (ref "U18") (pin "6") (pinfunction "SILENT_6") (pintype "input"))
    )
    (net (code "29") (name "/SLEEP") (class "Default")
      (node (ref "R157") (pin "1") (pinfunction "1_1") (pintype "passive"))
      (node (ref "U14") (pin "27") (pinfunction "~{SLEEP}_27") (pintype "passive"))
      (node (ref "U17") (pin "6") (pinfunction "B2_6") (pintype "passive"))
    )
    (net (code "30") (name "/SLEEP_ISO") (class "Default")
      (node (ref "U17") (pin "3") (pinfunction "A2_3") (pintype "passive"))
    )
    (net (code "31") (name "/SR") (class "Default")
      (node (ref "R158") (pin "1") (pinfunction "1_1") (pintype "passive"))
      (node (ref "U14") (pin "16") (pinfunction "~{SR}_16") (pintype "passive"))
      (node (ref "U16") (pin "6") (pinfunction "B2_6") (pintype "passive"))
    )
    (net (code "32") (name "/SR_ISO") (class "Default")
      (node (ref "U16") (pin "3") (pinfunction "A2_3") (pintype "passive"))
    )
    (net (code "33") (name "/STBY") (class "Default")
      (node (ref "U18") (pin "8") (pinfunction "STBY_8") (pintype "input"))
    )
    (net (code "34") (name "/STEP") (class "Default")
      (node (ref "U14") (pin "19") (pinfunction "STEP_19") (pintype "passive"))
      (node (ref "U17") (pin "7") (pinfunction "B1_7") (pintype "passive"))
    )
    (net (code "35") (name "/STEP_ISO") (class "Default")
      (node (ref "U17") (pin "2") (pinfunction "A1_2") (pintype "passive"))
    )
    (net (code "36") (name "/TXD") (class "Default")
      (node (ref "U18") (pin "7") (pinfunction "TXD_7") (pintype "input"))
    )
    (net (code "37") (name "/USM0") (class "Default")
      (node (ref "U14") (pin "13") (pinfunction "USM0_13") (pintype "passive"))
      (node (ref "U15") (pin "7") (pinfunction "B1_7") (pintype "passive"))
    )
    (net (code "38") (name "/USM0_ISO") (class "Default")
      (node (ref "U15") (pin "2") (pinfunction "A1_2") (pintype "passive"))
    )
    (net (code "39") (name "/USM1") (class "Default")
      (node (ref "U14") (pin "12") (pinfunction "USM1_12") (pintype "passive"))
      (node (ref "U15") (pin "6") (pinfunction "B2_6") (pintype "passive"))
    )
    (net (code "40") (name "/USM1_ISO") (class "Default")
      (node (ref "U15") (pin "3") (pinfunction "A2_3") (pintype "passive"))
    )
    (net (code "43") (name "GND") (class "Default")
      (node (ref "C363") (pin "2") (pinfunction "2_2") (pintype "passive"))
      (node (ref "C367") (pin "2") (pinfunction "2_2") (pintype "passive"))
      (node (ref "ISO1") (pin "3") (pinfunction "GND_3") (pintype "power_in"))
      (node (ref "U13") (pin "4") (pinfunction "GND1_4") (pintype "passive"))
      (node (ref "U15") (pin "4") (pinfunction "GND1_4") (pintype "passive"))
      (node (ref "U16") (pin "4") (pinfunction "GND1_4") (pintype "passive"))
      (node (ref "U17") (pin "4") (pinfunction "GND1_4") (pintype "passive"))
      (node (ref "U18") (pin "1") (pinfunction "GND1_1") (pintype "power_in"))
      (node (ref "U18") (pin "10") (pinfunction "GND1_10") (pintype "power_in"))
      (node (ref "U18") (pin "2") (pinfunction "GND1_2") (pintype "power_in"))
    )
    (net (code "44") (name "GND_CAN") (class "Default")
      (node (ref "C358") (pin "2") (pinfunction "2_2") (pintype "passive"))
      (node (ref "C359") (pin "2") (pinfunction "2_2") (pintype "passive"))
      (node (ref "C360") (pin "2") (pinfunction "2_2") (pintype "passive"))
      (node (ref "FB4") (pin "2") (pinfunction "2_2") (pintype "passive"))
      (node (ref "J12") (pin "4") (pinfunction "4_4") (pintype "passive"))
      (node (ref "Q4") (pin "2") (pinfunction "S_2") (pintype "passive"))
      (node (ref "R170") (pin "2") (pinfunction "2_2") (pintype "passive"))
      (node (ref "TP75") (pin "1") (pinfunction "A_1") (pintype "passive"))
      (node (ref "U18") (pin "11") (pinfunction "GND2_11") (pintype "power_in"))
      (node (ref "U18") (pin "15") (pinfunction "GND2_15") (pintype "power_in"))
    )
    (net (code "45") (name "GND_MOT") (class "Default")
      (node (ref "C339") (pin "2") (pinfunction "2_2") (pintype "passive"))
      (node (ref "C340") (pin "2") (pinfunction "2_2") (pintype "passive"))
      (node (ref "C341") (pin "2") (pinfunction "2_2") (pintype "passive"))
      (node (ref "C344") (pin "2") (pinfunction "2_2") (pintype "passive"))
      (node (ref "C345") (pin "2") (pinfunction "2_2") (pintype "passive"))
      (node (ref "C346") (pin "2") (pinfunction "2_2") (pintype "passive"))
      (node (ref "C347") (pin "2") (pinfunction "2_2") (pintype "passive"))
      (node (ref "C348") (pin "2") (pinfunction "2_2") (pintype "passive"))
      (node (ref "C349") (pin "2") (pinfunction "2_2") (pintype "passive"))
      (node (ref "C350") (pin "2") (pinfunction "2_2") (pintype "passive"))
      (node (ref "C351") (pin "2") (pinfunction "2_2") (pintype "passive"))
      (node (ref "C352") (pin "2") (pinfunction "2_2") (pintype "passive"))
      (node (ref "C353") (pin "2") (pinfunction "2_2") (pintype "passive"))
      (node (ref "C354") (pin "2") (pinfunction "2_2") (pintype "passive"))
      (node (ref "C355") (pin "2") (pinfunction "2_2") (pintype "passive"))
      (node (ref "C356") (pin "2") (pinfunction "2_2") (pintype "passive"))
      (node (ref "C357") (pin "2") (pinfunction "2_2") (pintype "passive"))
      (node (ref "D10") (pin "2") (pinfunction "C_2") (pintype "passive"))
      (node (ref "D11") (pin "2") (pinfunction "C_2") (pintype "passive"))
      (node (ref "D12") (pin "2") (pinfunction "C_2") (pintype "passive"))
      (node (ref "D13") (pin "2") (pinfunction "C_2") (pintype "passive"))
      (node (ref "D14") (pin "1") (pinfunction "A_1") (pintype "passive"))
      (node (ref "D15") (pin "1") (pinfunction "A_1") (pintype "passive"))
      (node (ref "D16") (pin "1") (pinfunction "A_1") (pintype "passive"))
      (node (ref "D17") (pin "1") (pinfunction "A_1") (pintype "passive"))
      (node (ref "HEAT3") (pin "1") (pintype "passive"))
      (node (ref "HEAT3") (pin "2") (pintype "passive"))
      (node (ref "ISO1") (pin "2") (pinfunction "CATHODE_2") (pintype "output"))
      (node (ref "Q3") (pin "2") (pinfunction "S_2") (pintype "passive"))
      (node (ref "R155") (pin "2") (pinfunction "2_2") (pintype "passive"))
      (node (ref "R156") (pin "2") (pinfunction "2_2") (pintype "passive"))
      (node (ref "R157") (pin "2") (pinfunction "2_2") (pintype "passive"))
      (node (ref "R158") (pin "2") (pinfunction "2_2") (pintype "passive"))
      (node (ref "R159") (pin "2") (pinfunction "2_2") (pintype "passive"))
      (node (ref "R163") (pin "2") (pinfunction "2_2") (pintype "passive"))
      (node (ref "R164") (pin "2") (pinfunction "2_2") (pintype "passive"))
      (node (ref "R165") (pin "2") (pinfunction "2_2") (pintype "passive"))
      (node (ref "R166") (pin "2") (pinfunction "2_2") (pintype "passive"))
      (node (ref "TP72") (pin "1") (pinfunction "A_1") (pintype "passive"))
      (node (ref "U13") (pin "5") (pinfunction "GND2_5") (pintype "passive"))
      (node (ref "U14") (pin "21") (pinfunction "GND_21") (pintype "passive"))
      (node (ref "U14") (pin "7") (pinfunction "GND_7") (pintype "passive"))
      (node (ref "U14") (pin "PAD") (pinfunction "GND_PAD") (pintype "passive"))
      (node (ref "U15") (pin "5") (pinfunction "GND2_5") (pintype "passive"))
      (node (ref "U16") (pin "5") (pinfunction "GND2_5") (pintype "passive"))
      (node (ref "U17") (pin "5") (pinfunction "GND2_5") (pintype "passive"))
    )
    (net (code "46") (name "Net-(C361-Pad2)") (class "Default")
      (node (ref "C361") (pin "2") (pinfunction "2_2") (pintype "passive"))
      (node (ref "C362") (pin "2") (pinfunction "2_2") (pintype "passive"))
      (node (ref "FB4") (pin "1") (pinfunction "1_1") (pintype "passive"))
      (node (ref "U18") (pin "18") (pinfunction "GNDISO_18") (pintype "power_in"))
      (node (ref "U18") (pin "20") (pinfunction "GNDISO_20") (pintype "power_in"))
    )
    (net (code "47") (name "Net-(D18-A)") (class "Default")
      (node (ref "D18") (pin "1") (pinfunction "A_1") (pintype "passive"))
      (node (ref "R167") (pin "2") (pinfunction "2_2") (pintype "passive"))
    )
    (net (code "48") (name "Net-(D18-K)") (class "Default")
      (node (ref "D18") (pin "2") (pinfunction "K_2") (pintype "passive"))
      (node (ref "Q4") (pin "3") (pinfunction "D_3") (pintype "passive"))
    )
    (net (code "49") (name "Net-(ISO1-ANODE)") (class "Default")
      (node (ref "ISO1") (pin "1") (pinfunction "ANODE_1") (pintype "input"))
      (node (ref "Q3") (pin "3") (pinfunction "D_3") (pintype "passive"))
      (node (ref "R160") (pin "1") (pinfunction "1_1") (pintype "passive"))
      (node (ref "R161") (pin "1") (pinfunction "1_1") (pintype "passive"))
    )
    (net (code "50") (name "Net-(J13-Pad2)") (class "Default")
      (node (ref "J13") (pin "2") (pinfunction "2_2") (pintype "passive"))
      (node (ref "R169") (pin "2") (pinfunction "2_2") (pintype "passive"))
    )
    (net (code "51") (name "Net-(U14A-CP1)") (class "Default")
      (node (ref "C343") (pin "1") (pinfunction "1_1") (pintype "passive"))
      (node (ref "U14") (pin "23") (pinfunction "CP1_23") (pintype "passive"))
    )
    (net (code "52") (name "Net-(U14A-CP2)") (class "Default")
      (node (ref "C343") (pin "2") (pinfunction "2_2") (pintype "passive"))
      (node (ref "U14") (pin "24") (pinfunction "CP2_24") (pintype "passive"))
    )
    (net (code "53") (name "Net-(U14A-VCP)") (class "Default")
      (node (ref "C342") (pin "1") (pinfunction "1_1") (pintype "passive"))
      (node (ref "U14") (pin "22") (pinfunction "VCP_22") (pintype "passive"))
    )
    (net (code "54") (name "Net-(U14A-VGD)") (class "Default")
      (node (ref "C345") (pin "1") (pinfunction "1_1") (pintype "passive"))
      (node (ref "U14") (pin "20") (pinfunction "VGD_20") (pintype "passive"))
    )
    (net (code "55") (name "Net-(U14A-VREF)") (class "Default")
      (node (ref "C340") (pin "1") (pinfunction "1_1") (pintype "passive"))
      (node (ref "R152") (pin "2") (pinfunction "2_2") (pintype "passive"))
      (node (ref "R155") (pin "1") (pinfunction "1_1") (pintype "passive"))
      (node (ref "U14") (pin "8") (pinfunction "VREF_8") (pintype "passive"))
    )
    (net (code "56") (name "Net-(U14B-ISENA)") (class "Default")
      (node (ref "R156") (pin "1") (pinfunction "1_1") (pintype "passive"))
      (node (ref "U14") (pin "1") (pinfunction "ISENA_1") (pintype "passive"))
    )
    (net (code "57") (name "Net-(U14C-ISENB)") (class "Default")
      (node (ref "R159") (pin "1") (pinfunction "1_1") (pintype "passive"))
      (node (ref "U14") (pin "14") (pinfunction "ISENB_14") (pintype "passive"))
    )
    (net (code "58") (name "Net-(U18-RS)") (class "Default")
      (node (ref "R170") (pin "1") (pinfunction "1_1") (pintype "passive"))
      (node (ref "U18") (pin "12") (pinfunction "RS_12") (pintype "input"))
    )
    (net (code "59") (name "Net-(U18-VISOOUT)") (class "Default")
      (node (ref "C361") (pin "1") (pinfunction "1_1") (pintype "passive"))
      (node (ref "C362") (pin "1") (pinfunction "1_1") (pintype "passive"))
      (node (ref "FB3") (pin "1") (pinfunction "1_1") (pintype "passive"))
      (node (ref "U18") (pin "19") (pinfunction "VISOOUT_19") (pintype "power_in"))
    )
  )
)
